# design.net
KiCad netlist of a schematic drawn in Altium Designer
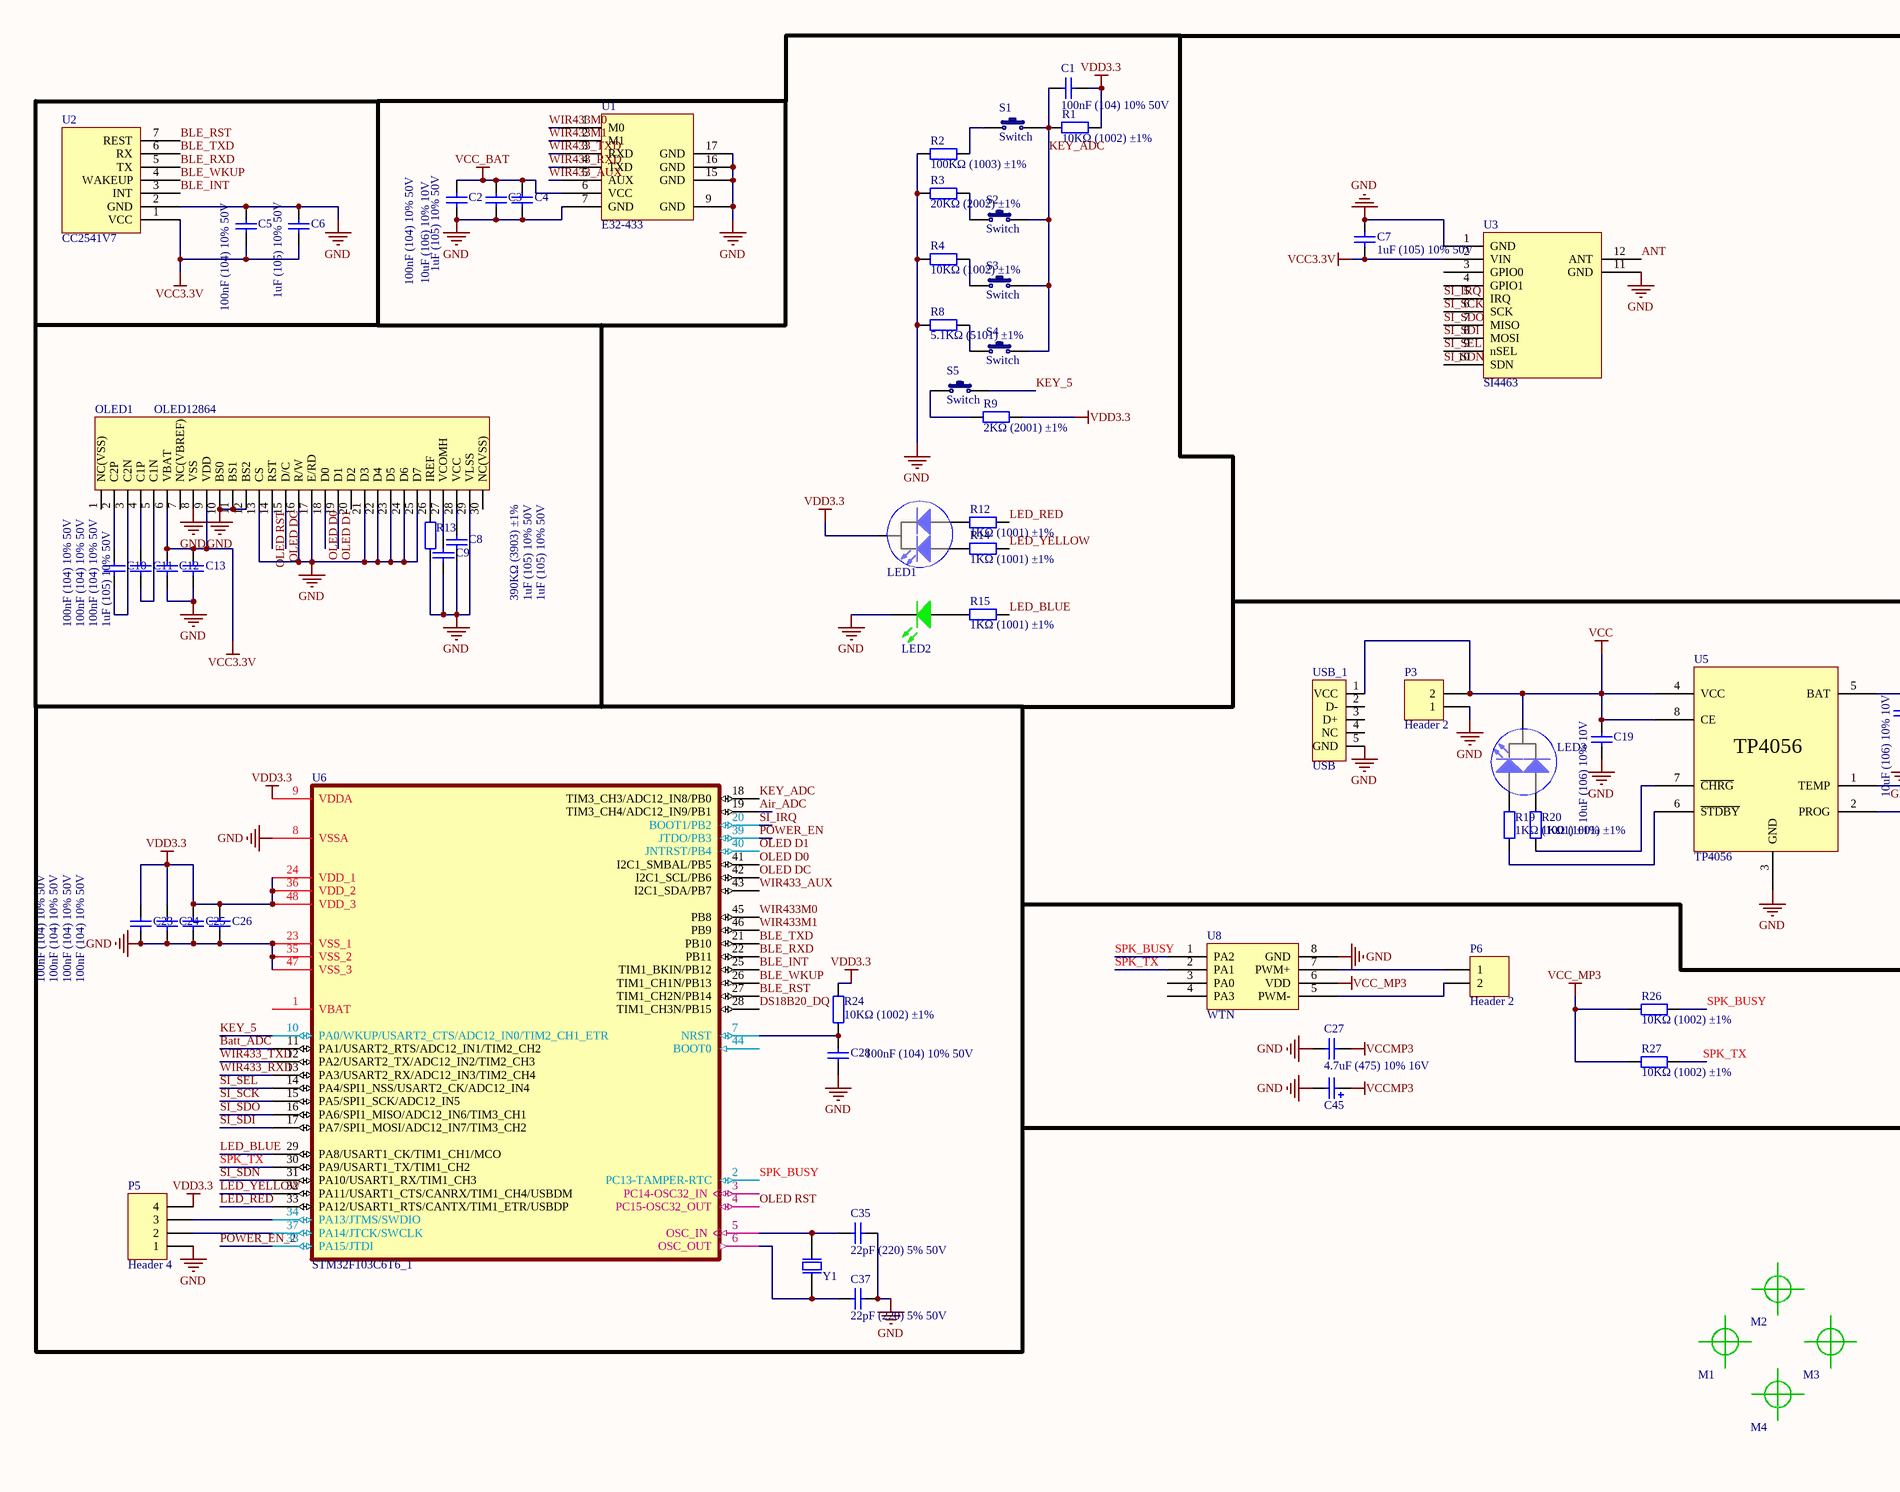
[diagram p0: 消防背表.SchDoc, left]
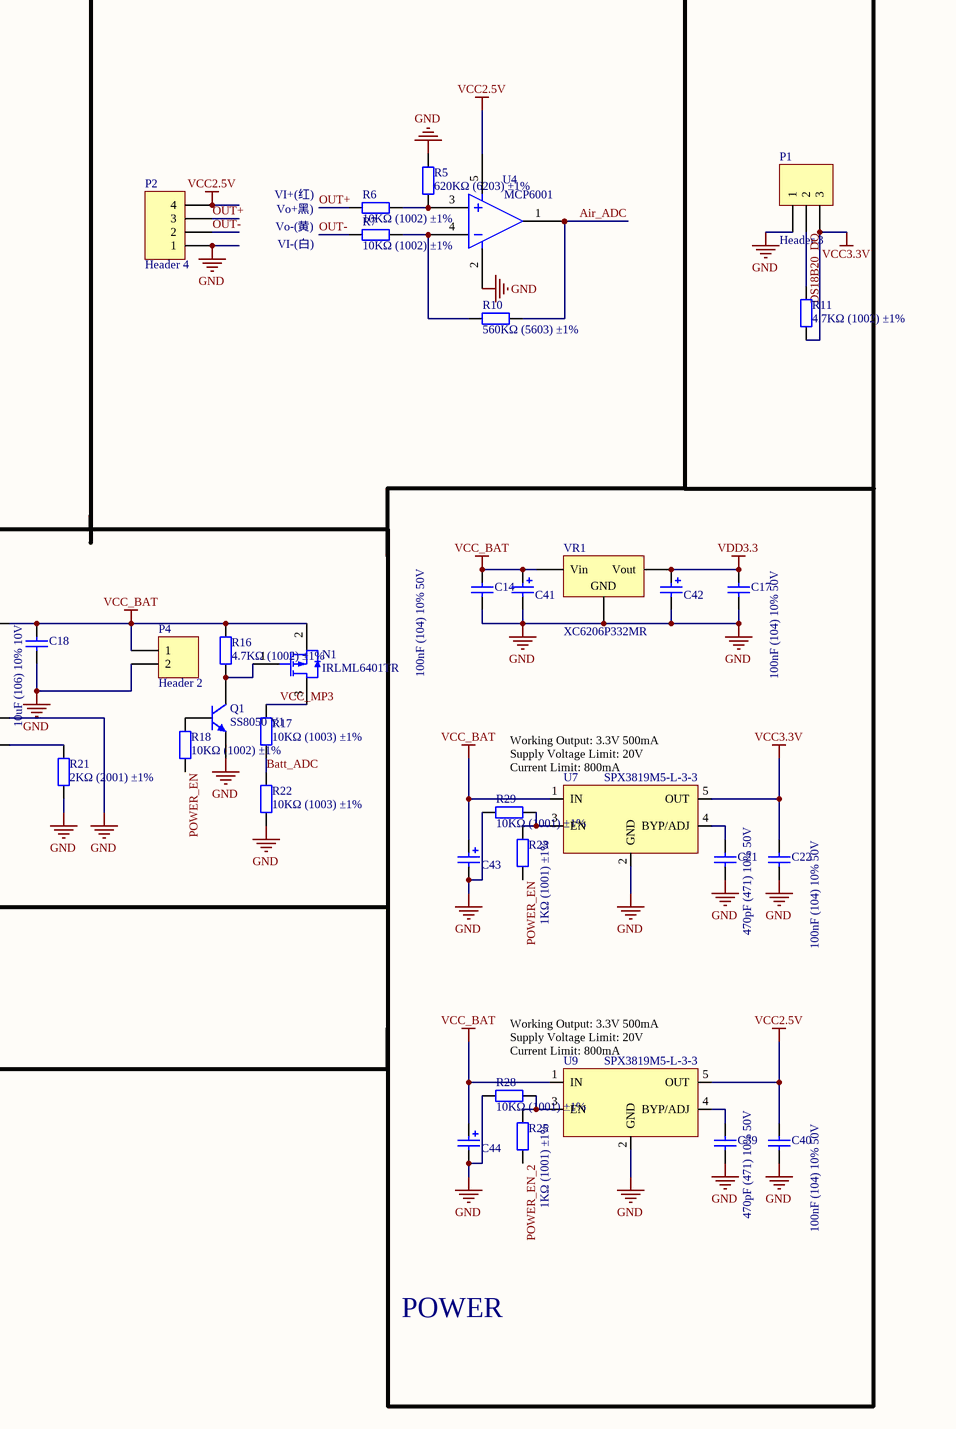
[diagram p1: 消防背表.SchDoc, right]

(export (version "E")
  (design (tool "Eeschema 10.0.6"))
  (components
    (comp (ref "C1")
      (value "100nF (104) 10% 50V")
      (footprint "0603_C")
      (description "贴片电容")
      (libsource (lib "Miscellaneous Devices LC ") (part "0603 100nF (104) 10% 50V"))
    )
    (comp (ref "C2")
      (value "1uF (105) 10% 50V")
      (footprint "0603_C")
      (description "贴片电容")
      (libsource (lib "Miscellaneous Devices LC ") (part "0603 1uF (105) 10% 50V"))
    )
    (comp (ref "C3")
      (value "10uF (106) 10% 10V")
      (footprint "0603_C")
      (description "贴片电容")
      (libsource (lib "Miscellaneous Devices LC ") (part "0603 10uF (106) 10% 10V"))
    )
    (comp (ref "C4")
      (value "100nF (104) 10% 50V")
      (footprint "0603_C")
      (description "贴片电容")
      (libsource (lib "Miscellaneous Devices LC ") (part "0603 100nF (104) 10% 50V"))
    )
    (comp (ref "C5")
      (value "100nF (104) 10% 50V")
      (footprint "0603_C")
      (description "贴片电容")
      (libsource (lib "Miscellaneous Devices LC ") (part "0603 100nF (104) 10% 50V"))
    )
    (comp (ref "C6")
      (value "1uF (105) 10% 50V")
      (footprint "0603_C")
      (description "贴片电容")
      (libsource (lib "Miscellaneous Devices LC ") (part "0603 1uF (105) 10% 50V"))
    )
    (comp (ref "C7")
      (value "1uF (105) 10% 50V")
      (footprint "0603_C")
      (description "贴片电容")
      (libsource (lib "Miscellaneous Devices LC ") (part "0603 1uF (105) 10% 50V"))
    )
    (comp (ref "C8")
      (value "1uF (105) 10% 50V")
      (footprint "0603_C")
      (description "贴片电容")
      (libsource (lib "Miscellaneous Devices LC ") (part "0603 1uF (105) 10% 50V"))
    )
    (comp (ref "C9")
      (value "1uF (105) 10% 50V")
      (footprint "0603_C")
      (description "贴片电容")
      (libsource (lib "Miscellaneous Devices LC ") (part "0603 1uF (105) 10% 50V"))
    )
    (comp (ref "C10")
      (value "100nF (104) 10% 50V")
      (footprint "0603_C")
      (description "贴片电容")
      (libsource (lib "Miscellaneous Devices LC ") (part "0603 100nF (104) 10% 50V"))
    )
    (comp (ref "C11")
      (value "100nF (104) 10% 50V")
      (footprint "0603_C")
      (description "贴片电容")
      (libsource (lib "Miscellaneous Devices LC ") (part "0603 100nF (104) 10% 50V"))
    )
    (comp (ref "C12")
      (value "100nF (104) 10% 50V")
      (footprint "0603_C")
      (description "贴片电容")
      (libsource (lib "Miscellaneous Devices LC ") (part "0603 100nF (104) 10% 50V"))
    )
    (comp (ref "C13")
      (value "1uF (105) 10% 50V")
      (footprint "0603_C")
      (description "贴片电容")
      (libsource (lib "Miscellaneous Devices LC ") (part "0603 1uF (105) 10% 50V"))
    )
    (comp (ref "C14")
      (value "100nF (104) 10% 50V")
      (footprint "0603_C")
      (description "贴片电容")
      (libsource (lib "Miscellaneous Devices LC ") (part "0603 100nF (104) 10% 50V"))
    )
    (comp (ref "C17")
      (value "100nF (104) 10% 50V")
      (footprint "0603_C")
      (description "贴片电容")
      (libsource (lib "Miscellaneous Devices LC ") (part "0603 100nF (104) 10% 50V"))
    )
    (comp (ref "C18")
      (value "10uF (106) 10% 10V")
      (footprint "0603_C")
      (description "贴片电容")
      (libsource (lib "Miscellaneous Devices LC ") (part "0603 10uF (106) 10% 10V"))
    )
    (comp (ref "C19")
      (value "10uF (106) 10% 10V")
      (footprint "0603_C")
      (description "贴片电容")
      (libsource (lib "Miscellaneous Devices LC ") (part "0603 10uF (106) 10% 10V"))
    )
    (comp (ref "C21")
      (value "470pF (471) 10% 50V")
      (footprint "0603_C")
      (description "贴片电容")
      (libsource (lib "Miscellaneous Devices LC ") (part "0603 470pF (471) 10% 50V"))
    )
    (comp (ref "C22")
      (value "100nF (104) 10% 50V")
      (footprint "0603_C")
      (description "贴片电容")
      (libsource (lib "Miscellaneous Devices LC ") (part "0603 100nF (104) 10% 50V"))
    )
    (comp (ref "C23")
      (value "100nF (104) 10% 50V")
      (footprint "0603_C")
      (description "贴片电容")
      (libsource (lib "Miscellaneous Devices LC ") (part "0603 100nF (104) 10% 50V"))
    )
    (comp (ref "C24")
      (value "100nF (104) 10% 50V")
      (footprint "0603_C")
      (description "贴片电容")
      (libsource (lib "Miscellaneous Devices LC ") (part "0603 100nF (104) 10% 50V"))
    )
    (comp (ref "C25")
      (value "100nF (104) 10% 50V")
      (footprint "0603_C")
      (description "贴片电容")
      (libsource (lib "Miscellaneous Devices LC ") (part "0603 100nF (104) 10% 50V"))
    )
    (comp (ref "C26")
      (value "100nF (104) 10% 50V")
      (footprint "0603_C")
      (description "贴片电容")
      (libsource (lib "Miscellaneous Devices LC ") (part "0603 100nF (104) 10% 50V"))
    )
    (comp (ref "C27")
      (value "4.7uF (475) 10% 16V")
      (footprint "0603_C")
      (description "贴片电容")
      (libsource (lib "Miscellaneous Devices LC ") (part "0603 4.7uF (475) 10% 16V"))
    )
    (comp (ref "C28")
      (value "100nF (104) 10% 50V")
      (footprint "0603_C")
      (description "贴片电容")
      (libsource (lib "Miscellaneous Devices LC ") (part "0603 100nF (104) 10% 50V"))
    )
    (comp (ref "C35")
      (value "22pF (220) 5% 50V")
      (footprint "0603_C")
      (description "贴片电容")
      (libsource (lib "Miscellaneous Devices LC ") (part "0603 22pF (220) 5% 50V"))
    )
    (comp (ref "C37")
      (value "22pF (220) 5% 50V")
      (footprint "0603_C")
      (description "贴片电容")
      (libsource (lib "Miscellaneous Devices LC ") (part "0603 22pF (220) 5% 50V"))
    )
    (comp (ref "C39")
      (value "470pF (471) 10% 50V")
      (footprint "0603_C")
      (description "贴片电容")
      (libsource (lib "Miscellaneous Devices LC ") (part "0603 470pF (471) 10% 50V"))
    )
    (comp (ref "C40")
      (value "100nF (104) 10% 50V")
      (footprint "0603_C")
      (description "贴片电容")
      (libsource (lib "Miscellaneous Devices LC ") (part "0603 100nF (104) 10% 50V"))
    )
    (comp (ref "C41")
      (value "Cap Tan")
      (footprint "TAN-A-3216")
      (description "Polarized Capacitor (Radial)")
      (fields (field (name "VOLTAGE") "16V") (field (name "PUBLISHER") "Altium Limited"))
      (libsource (lib "(NEW)DRC_MD Library") (part "Cap Tan"))
    )
    (comp (ref "C42")
      (value "Cap Tan")
      (footprint "TAN-A-3216")
      (description "Polarized Capacitor (Radial)")
      (fields (field (name "VOLTAGE") "16V") (field (name "PUBLISHER") "Altium Limited"))
      (libsource (lib "(NEW)DRC_MD Library") (part "Cap Tan"))
    )
    (comp (ref "C43")
      (value "Cap Tan")
      (footprint "TAN-A-3216")
      (description "Polarized Capacitor (Radial)")
      (fields (field (name "VOLTAGE") "16V") (field (name "PUBLISHER") "Altium Limited"))
      (libsource (lib "(NEW)DRC_MD Library") (part "Cap Tan"))
    )
    (comp (ref "C44")
      (value "Cap Tan")
      (footprint "TAN-A-3216")
      (description "Polarized Capacitor (Radial)")
      (fields (field (name "VOLTAGE") "16V") (field (name "PUBLISHER") "Altium Limited"))
      (libsource (lib "(NEW)DRC_MD Library") (part "Cap Tan"))
    )
    (comp (ref "C45")
      (value "Cap Tan")
      (footprint "TAN-A-3216")
      (description "Polarized Capacitor (Radial)")
      (fields (field (name "VOLTAGE") "16V") (field (name "PUBLISHER") "Altium Limited"))
      (libsource (lib "(NEW)DRC_MD Library") (part "Cap Tan"))
    )
    (comp (ref "LED1")
      (value "LED-3-DOUBLE")
      (footprint "LED-R3-H5-DOUBLE")
      (description "Typical INFRARED GaAs LED")
      (fields (field (name "PUBLISHER") "Altium Limited"))
      (libsource (lib "(NEW)DRC_MD Library") (part "LED-3-DOUBLE"))
    )
    (comp (ref "LED2")
      (value "LED-3-G")
      (footprint "LED-R3-H5-SINGLE-G")
      (description "Typical INFRARED GaAs LED")
      (fields (field (name "PUBLISHER") "Altium Limited"))
      (libsource (lib "(NEW)DRC_MD Library") (part "LED-3-G"))
    )
    (comp (ref "LED3")
      (value "LED-3-DOUBLE")
      (footprint "LED-R3-H5-DOUBLE")
      (description "Typical INFRARED GaAs LED")
      (fields (field (name "PUBLISHER") "Altium Limited"))
      (libsource (lib "(NEW)DRC_MD Library") (part "LED-3-DOUBLE"))
    )
    (comp (ref "M1")
      (value "Screw Hole")
      (footprint "Screw hexagon 3mm")
      (libsource (lib "(NEW)DRC_MD Library") (part "Screw Hole"))
    )
    (comp (ref "M2")
      (value "Screw Hole")
      (footprint "Screw hexagon 3mm")
      (libsource (lib "(NEW)DRC_MD Library") (part "Screw Hole"))
    )
    (comp (ref "M3")
      (value "Screw Hole")
      (footprint "Screw hexagon 3mm")
      (libsource (lib "(NEW)DRC_MD Library") (part "Screw Hole"))
    )
    (comp (ref "M4")
      (value "Screw Hole")
      (footprint "Screw hexagon 3mm")
      (libsource (lib "(NEW)DRC_MD Library") (part "Screw Hole"))
    )
    (comp (ref "N1")
      (value "IRLML6401TR")
      (footprint "SOT23-3")
      (fields (field (name "Comment") "P-MOS"))
      (libsource (lib "kooloo_V1.0") (part "P-MOS"))
    )
    (comp (ref "OLED1")
      (value "OLED12864")
      (footprint "OLED_0.96")
      (libsource (lib "封装库整理") (part "OLED12864"))
    )
    (comp (ref "P1")
      (value "Header 3")
      (footprint "HX2.54-3")
      (description "Header, 3-Pin")
      (fields (field (name "PUBLISHER") "Altium Limited"))
      (libsource (lib "(NEW)DRC_MD Library") (part "Header 3"))
    )
    (comp (ref "P2")
      (value "Header 4")
      (footprint "HX2.54-4")
      (description "Header, 4-Pin")
      (fields (field (name "PUBLISHER") "Altium Limited"))
      (libsource (lib "(NEW)DRC_MD Library") (part "Header 4"))
    )
    (comp (ref "P3")
      (value "Header 2")
      (footprint "HDR1X2")
      (description "Header, 2-Pin")
      (fields (field (name "PUBLISHER") "Altium Limited"))
      (libsource (lib "(NEW)DRC_MD Library") (part "Header 2"))
    )
    (comp (ref "P4")
      (value "Header 2")
      (footprint "HDR1X2")
      (description "Header, 2-Pin")
      (fields (field (name "PUBLISHER") "Altium Limited"))
      (libsource (lib "") (part "Header 2_1"))
    )
    (comp (ref "P5")
      (value "Header 4")
      (footprint "HDR1X4")
      (description "Header, 4-Pin")
      (fields (field (name "PUBLISHER") "Altium Limited"))
      (libsource (lib "(NEW)DRC_MD Library") (part "Header 4"))
    )
    (comp (ref "P6")
      (value "Header 2")
      (footprint "HDR1X2")
      (description "Header, 2-Pin")
      (fields (field (name "PUBLISHER") "Altium Limited"))
      (libsource (lib "") (part "Header 2_1"))
    )
    (comp (ref "Q1")
      (value "SS8050 Y1")
      (footprint "SOT-23(SOT-23-3)")
      (description "三极管")
      (libsource (lib "Miscellaneous Devices LC ") (part "SOT-23 SS8050 Y1"))
    )
    (comp (ref "R1")
      (value "10KΩ (1002) ±1%")
      (footprint "0603_R")
      (description "贴片电阻")
      (libsource (lib "") (part "0603 10KΩ (1002) 1%_1"))
    )
    (comp (ref "R2")
      (value "100KΩ (1003) ±1%")
      (footprint "0603_R")
      (description "贴片电阻")
      (libsource (lib "") (part "0603 100KΩ (1003) 1%_1"))
    )
    (comp (ref "R3")
      (value "20KΩ (2002) ±1%")
      (footprint "0603_R")
      (description "贴片电阻")
      (libsource (lib "Miscellaneous Devices LC ") (part "0603 20KΩ (2002) 1%"))
    )
    (comp (ref "R4")
      (value "10KΩ (1002) ±1%")
      (footprint "0603_R")
      (description "贴片电阻")
      (libsource (lib "") (part "0603 10KΩ (1002) 1%_1"))
    )
    (comp (ref "R5")
      (value "620KΩ (6203) ±1%")
      (footprint "0603_R")
      (description "贴片电阻")
      (libsource (lib "Miscellaneous Devices LC ") (part "0603 620KΩ (6203) 1%"))
    )
    (comp (ref "R6")
      (value "10KΩ (1002) ±1%")
      (footprint "0603_R")
      (description "贴片电阻")
      (libsource (lib "") (part "0603 10KΩ (1002) 1%_1"))
    )
    (comp (ref "R7")
      (value "10KΩ (1002) ±1%")
      (footprint "0603_R")
      (description "贴片电阻")
      (libsource (lib "") (part "0603 10KΩ (1002) 1%_1"))
    )
    (comp (ref "R8")
      (value "5.1KΩ (5101) ±1%")
      (footprint "0603_R")
      (description "贴片电阻")
      (libsource (lib "Miscellaneous Devices LC ") (part "0603 5.1KΩ (5101) 1%"))
    )
    (comp (ref "R9")
      (value "2KΩ (2001) ±1%")
      (footprint "0603_R")
      (description "贴片电阻")
      (libsource (lib "Miscellaneous Devices LC ") (part "0603 2KΩ (2001) 1%"))
    )
    (comp (ref "R10")
      (value "560KΩ (5603) ±1%")
      (footprint "0603_R")
      (description "贴片电阻")
      (libsource (lib "Miscellaneous Devices LC ") (part "0603 560KΩ (5603) 1%"))
    )
    (comp (ref "R11")
      (value "4.7KΩ (1002) ±1%")
      (footprint "0603_R")
      (description "贴片电阻")
      (libsource (lib "Miscellaneous Devices LC ") (part "0603 10KΩ (1002) 1%"))
    )
    (comp (ref "R12")
      (value "1KΩ (1001) ±1%")
      (footprint "0603_R")
      (description "贴片电阻")
      (libsource (lib "Miscellaneous Devices LC ") (part "0603 1KΩ (1001) 1%"))
    )
    (comp (ref "R13")
      (value "390KΩ (3903) ±1%")
      (footprint "0603_R")
      (description "贴片电阻")
      (libsource (lib "Miscellaneous Devices LC ") (part "0603 390KΩ (3903) 1%"))
    )
    (comp (ref "R14")
      (value "1KΩ (1001) ±1%")
      (footprint "0603_R")
      (description "贴片电阻")
      (libsource (lib "Miscellaneous Devices LC ") (part "0603 1KΩ (1001) 1%"))
    )
    (comp (ref "R15")
      (value "1KΩ (1001) ±1%")
      (footprint "0603_R")
      (description "贴片电阻")
      (libsource (lib "Miscellaneous Devices LC ") (part "0603 1KΩ (1001) 1%"))
    )
    (comp (ref "R16")
      (value "4.7KΩ (1002) ±1%")
      (footprint "0603_R")
      (description "贴片电阻")
      (libsource (lib "Miscellaneous Devices LC ") (part "0603 10KΩ (1002) 1%"))
    )
    (comp (ref "R17")
      (value "10KΩ (1003) ±1%")
      (footprint "0603_R")
      (description "贴片电阻")
      (libsource (lib "Miscellaneous Devices LC ") (part "0603 100KΩ (1003) 1%"))
    )
    (comp (ref "R18")
      (value "10KΩ (1002) ±1%")
      (footprint "0603_R")
      (description "贴片电阻")
      (libsource (lib "Miscellaneous Devices LC ") (part "0603 10KΩ (1002) 1%"))
    )
    (comp (ref "R19")
      (value "1KΩ (1001) ±1%")
      (footprint "0603_R")
      (description "贴片电阻")
      (libsource (lib "") (part "0603 1KΩ (1001) 1%_2"))
    )
    (comp (ref "R20")
      (value "1KΩ (1001) ±1%")
      (footprint "0603_R")
      (description "贴片电阻")
      (libsource (lib "") (part "0603 1KΩ (1001) 1%_2"))
    )
    (comp (ref "R21")
      (value "2KΩ (2001) ±1%")
      (footprint "0603_R")
      (description "贴片电阻")
      (libsource (lib "") (part "0603 2KΩ (2001) 1%_1"))
    )
    (comp (ref "R22")
      (value "10KΩ (1003) ±1%")
      (footprint "0603_R")
      (description "贴片电阻")
      (libsource (lib "Miscellaneous Devices LC ") (part "0603 100KΩ (1003) 1%"))
    )
    (comp (ref "R23")
      (value "1KΩ (1001) ±1%")
      (footprint "0603_R")
      (description "贴片电阻")
      (libsource (lib "") (part "0603 1KΩ (1001) 1%_3"))
    )
    (comp (ref "R24")
      (value "10KΩ (1002) ±1%")
      (footprint "0603_R")
      (description "贴片电阻")
      (libsource (lib "") (part "0603 10KΩ (1002) 1%_2"))
    )
    (comp (ref "R25")
      (value "1KΩ (1001) ±1%")
      (footprint "0603_R")
      (description "贴片电阻")
      (libsource (lib "") (part "0603 1KΩ (1001) 1%_3"))
    )
    (comp (ref "R26")
      (value "10KΩ (1002) ±1%")
      (footprint "0603_R")
      (description "贴片电阻")
      (libsource (lib "Miscellaneous Devices LC ") (part "0603 1KΩ (1001) 1%"))
    )
    (comp (ref "R27")
      (value "10KΩ (1002) ±1%")
      (footprint "0603_R")
      (description "贴片电阻")
      (libsource (lib "Miscellaneous Devices LC ") (part "0603 1KΩ (1001) 1%"))
    )
    (comp (ref "R28")
      (value "10KΩ (1001) ±1%")
      (footprint "0603_R")
      (description "贴片电阻")
      (libsource (lib "") (part "0603 1KΩ (1001) 1%_1"))
    )
    (comp (ref "R29")
      (value "10KΩ (1001) ±1%")
      (footprint "0603_R")
      (description "贴片电阻")
      (libsource (lib "") (part "0603 1KΩ (1001) 1%_1"))
    )
    (comp (ref "S1") (value "Switch") (footprint "Switch1") (libsource (lib "Common Device") (part "Switch")))
    (comp (ref "S2") (value "Switch") (footprint "Switch1") (libsource (lib "Common Device") (part "Switch")))
    (comp (ref "S3") (value "Switch") (footprint "Switch1") (libsource (lib "Common Device") (part "Switch")))
    (comp (ref "S4") (value "Switch") (footprint "Switch1") (libsource (lib "Common Device") (part "Switch")))
    (comp (ref "S5") (value "Switch") (footprint "Switch1") (libsource (lib "Common Device") (part "Switch")))
    (comp (ref "U1") (value "E32-433") (footprint "E32_433") (libsource (lib "si4455") (part "E32-433")))
    (comp (ref "U2") (value "CC2541V7") (footprint "BLE_CC2451") (libsource (lib "si4455") (part "CC2541V7")))
    (comp (ref "U3") (value "SI4463") (footprint "SI4463") (libsource (lib "si4455") (part "SI4463")))
    (comp (ref "U4") (value "MCP6001") (footprint "SOT23-5") (libsource (lib "kooloo_V1.0") (part "MCP6001")))
    (comp (ref "U5") (value "TP4056") (footprint "SOP-8_150mil") (libsource (lib "shenj") (part "TP4056")))
    (comp (ref "U6")
      (value "STM32F103C6T6_1")
      (footprint "LQFP-48")
      (description "STM32 ARM-based 32-bit MCU with 32 Kbytes Flash, 48-pin LQFP, Industrial Temperature")
      (fields (field (name "PUBLISHER") "*"))
      (libsource (lib "元件库") (part "STM32F103C6T6_1"))
    )
    (comp (ref "U7")
      (value "SPX3819M5-L-3-3")
      (footprint "SOT-23-6")
      (description "500mA, Low-Noise LDO Voltage Regulator")
      (libsource (lib "Vowstar_IC_General") (part "SPX3819"))
    )
    (comp (ref "U8") (value "WTN") (footprint "SOP-8_150mil") (libsource (lib "si4455") (part "WTN6")))
    (comp (ref "U9")
      (value "SPX3819M5-L-3-3")
      (footprint "SOT-23-6")
      (description "500mA, Low-Noise LDO Voltage Regulator")
      (libsource (lib "Vowstar_IC_General") (part "SPX3819"))
    )
    (comp (ref "USB_1")
      (value "USB")
      (footprint "USB-MINI-B")
      (libsource (lib "(NEW)DRC_MD Library") (part "USB5"))
    )
    (comp (ref "VR1")
      (value "XC6206P332MR")
      (footprint "SOT-23-3L")
      (description "低压差线性稳压(LDO)")
      (libsource (lib "Miscellaneous Devices LC ") (part "SOT-23 XC6206P332MR"))
    )
    (comp (ref "Y1")
      (value "XTAL")
      (footprint "XTAL-49/U_N")
      (description "Crystal Oscillator")
      (fields (field (name "PUBLISHER") "Altium Limited"))
      (libsource (lib "(NEW)DRC_MD Library") (part "XTAL"))
    )
  )
  (nets
    (net (code "1") (name "/ANT") (class "Default")
      (node (ref "U3") (pin "12") (pinfunction "ANT_12") (pintype "passive"))
    )
    (net (code "2") (name "/Air_ADC") (class "Default")
      (node (ref "R10") (pin "2") (pinfunction "2_2") (pintype "passive"))
      (node (ref "U4") (pin "1") (pintype "passive"))
      (node (ref "U6") (pin "19") (pinfunction "TIM3_CH4/ADC12_IN9/PB1_19") (pintype "bidirectional"))
    )
    (net (code "3") (name "/BLE_INT") (class "Default")
      (node (ref "U2") (pin "3") (pinfunction "INT_3") (pintype "passive"))
      (node (ref "U6") (pin "25") (pinfunction "TIM1_BKIN/PB12_25") (pintype "bidirectional"))
    )
    (net (code "4") (name "/BLE_RST") (class "Default")
      (node (ref "U2") (pin "7") (pinfunction "REST_7") (pintype "passive"))
      (node (ref "U6") (pin "27") (pinfunction "TIM1_CH2N/PB14_27") (pintype "bidirectional"))
    )
    (net (code "5") (name "/BLE_RXD") (class "Default")
      (node (ref "U2") (pin "5") (pinfunction "TX_5") (pintype "passive"))
      (node (ref "U6") (pin "22") (pinfunction "PB11_22") (pintype "bidirectional"))
    )
    (net (code "6") (name "/BLE_TXD") (class "Default")
      (node (ref "U2") (pin "6") (pinfunction "RX_6") (pintype "passive"))
      (node (ref "U6") (pin "21") (pinfunction "PB10_21") (pintype "bidirectional"))
    )
    (net (code "7") (name "/BLE_WKUP") (class "Default")
      (node (ref "U2") (pin "4") (pinfunction "WAKEUP_4") (pintype "passive"))
      (node (ref "U6") (pin "26") (pinfunction "TIM1_CH1N/PB13_26") (pintype "bidirectional"))
    )
    (net (code "8") (name "/Batt_ADC") (class "Default")
      (node (ref "R17") (pin "1") (pinfunction "1_1") (pintype "passive"))
      (node (ref "R22") (pin "2") (pinfunction "2_2") (pintype "passive"))
      (node (ref "U6") (pin "11") (pinfunction "PA1/USART2_RTS/ADC12_IN1/TIM2_CH2_11") (pintype "bidirectional"))
    )
    (net (code "9") (name "/DS18B20_DQ") (class "Default")
      (node (ref "P1") (pin "2") (pinfunction "2_2") (pintype "passive"))
      (node (ref "R11") (pin "1") (pinfunction "1_1") (pintype "passive"))
      (node (ref "U6") (pin "28") (pinfunction "TIM1_CH3N/PB15_28") (pintype "bidirectional"))
    )
    (net (code "10") (name "/KEY_5") (class "Default")
      (node (ref "S5") (pin "2") (pinfunction "1_2") (pintype "passive"))
      (node (ref "U6") (pin "10") (pinfunction "PA0/WKUP/USART2_CTS/ADC12_IN0/TIM2_CH1_ETR_10") (pintype "bidirectional"))
    )
    (net (code "11") (name "/KEY_ADC") (class "Default")
      (node (ref "C1") (pin "2") (pinfunction "2_2") (pintype "passive"))
      (node (ref "R1") (pin "1") (pinfunction "1_1") (pintype "passive"))
      (node (ref "S1") (pin "2") (pinfunction "1_2") (pintype "passive"))
      (node (ref "S2") (pin "2") (pinfunction "1_2") (pintype "passive"))
      (node (ref "S3") (pin "2") (pinfunction "1_2") (pintype "passive"))
      (node (ref "S4") (pin "2") (pinfunction "1_2") (pintype "passive"))
      (node (ref "U6") (pin "18") (pinfunction "TIM3_CH3/ADC12_IN8/PB0_18") (pintype "bidirectional"))
    )
    (net (code "12") (name "/LED_BLUE") (class "Default")
      (node (ref "R15") (pin "1") (pinfunction "1_1") (pintype "passive"))
      (node (ref "U6") (pin "29") (pinfunction "PA8/USART1_CK/TIM1_CH1/MCO_29") (pintype "bidirectional"))
    )
    (net (code "13") (name "/LED_RED") (class "Default")
      (node (ref "R12") (pin "1") (pinfunction "1_1") (pintype "passive"))
      (node (ref "U6") (pin "33") (pinfunction "PA12/USART1_RTS/CANTX/TIM1_ETR/USBDP_33") (pintype "bidirectional"))
    )
    (net (code "14") (name "/LED_YELLOW") (class "Default")
      (node (ref "R14") (pin "1") (pinfunction "1_1") (pintype "passive"))
      (node (ref "U6") (pin "32") (pinfunction "PA11/USART1_CTS/CANRX/TIM1_CH4/USBDM_32") (pintype "bidirectional"))
    )
    (net (code "15") (name "/OLED D0") (class "Default")
      (node (ref "OLED1") (pin "18") (pinfunction "D0_18") (pintype "passive"))
      (node (ref "U6") (pin "41") (pinfunction "I2C1_SMBAL/PB5_41") (pintype "bidirectional"))
    )
    (net (code "16") (name "/OLED D1") (class "Default")
      (node (ref "OLED1") (pin "19") (pinfunction "D1_19") (pintype "passive"))
      (node (ref "U6") (pin "40") (pinfunction "JNTRST/PB4_40") (pintype "bidirectional"))
    )
    (net (code "17") (name "/OLED DC") (class "Default")
      (node (ref "OLED1") (pin "15") (pinfunction "D/C_15") (pintype "passive"))
      (node (ref "U6") (pin "42") (pinfunction "I2C1_SCL/PB6_42") (pintype "bidirectional"))
    )
    (net (code "18") (name "/OLED RST") (class "Default")
      (node (ref "OLED1") (pin "14") (pinfunction "RST_14") (pintype "passive"))
      (node (ref "U6") (pin "4") (pinfunction "PC15-OSC32_OUT_4") (pintype "bidirectional"))
    )
    (net (code "19") (name "/OUT+") (class "Default")
      (node (ref "P2") (pin "3") (pinfunction "3_3") (pintype "passive"))
      (node (ref "R6") (pin "1") (pinfunction "1_1") (pintype "passive"))
    )
    (net (code "20") (name "/OUT-") (class "Default")
      (node (ref "P2") (pin "2") (pinfunction "2_2") (pintype "passive"))
      (node (ref "R7") (pin "1") (pinfunction "1_1") (pintype "passive"))
    )
    (net (code "21") (name "/POWER_EN") (class "Default")
      (node (ref "R18") (pin "2") (pinfunction "2_2") (pintype "passive"))
      (node (ref "R23") (pin "2") (pinfunction "2_2") (pintype "passive"))
      (node (ref "U6") (pin "39") (pinfunction "JTDO/PB3_39") (pintype "bidirectional"))
    )
    (net (code "22") (name "/POWER_EN_2") (class "Default")
      (node (ref "R25") (pin "2") (pinfunction "2_2") (pintype "passive"))
      (node (ref "U6") (pin "38") (pinfunction "PA15/JTDI_38") (pintype "bidirectional"))
    )
    (net (code "23") (name "/SI_IRQ") (class "Default")
      (node (ref "U3") (pin "5") (pinfunction "IRQ_5") (pintype "passive"))
      (node (ref "U6") (pin "20") (pinfunction "BOOT1/PB2_20") (pintype "bidirectional"))
    )
    (net (code "24") (name "/SI_SCK") (class "Default")
      (node (ref "U3") (pin "6") (pinfunction "SCK_6") (pintype "passive"))
      (node (ref "U6") (pin "15") (pinfunction "PA5/SPI1_SCK/ADC12_IN5_15") (pintype "bidirectional"))
    )
    (net (code "25") (name "/SI_SDI") (class "Default")
      (node (ref "U3") (pin "8") (pinfunction "MOSI_8") (pintype "passive"))
      (node (ref "U6") (pin "17") (pinfunction "PA7/SPI1_MOSI/ADC12_IN7/TIM3_CH2_17") (pintype "bidirectional"))
    )
    (net (code "26") (name "/SI_SDN") (class "Default")
      (node (ref "U3") (pin "10") (pinfunction "SDN_10") (pintype "passive"))
      (node (ref "U6") (pin "31") (pinfunction "PA10/USART1_RX/TIM1_CH3_31") (pintype "bidirectional"))
    )
    (net (code "27") (name "/SI_SDO") (class "Default")
      (node (ref "U3") (pin "7") (pinfunction "MISO_7") (pintype "passive"))
      (node (ref "U6") (pin "16") (pinfunction "PA6/SPI1_MISO/ADC12_IN6/TIM3_CH1_16") (pintype "bidirectional"))
    )
    (net (code "28") (name "/SI_SEL") (class "Default")
      (node (ref "U3") (pin "9") (pinfunction "nSEL_9") (pintype "passive"))
      (node (ref "U6") (pin "14") (pinfunction "PA4/SPI1_NSS/USART2_CK/ADC12_IN4_14") (pintype "bidirectional"))
    )
    (net (code "29") (name "/SPK_BUSY") (class "Default")
      (node (ref "R26") (pin "1") (pinfunction "1_1") (pintype "passive"))
      (node (ref "U6") (pin "2") (pinfunction "PC13-TAMPER-RTC_2") (pintype "bidirectional"))
      (node (ref "U8") (pin "1") (pinfunction "PA2_1") (pintype "passive"))
    )
    (net (code "30") (name "/SPK_TX") (class "Default")
      (node (ref "R27") (pin "1") (pinfunction "1_1") (pintype "passive"))
      (node (ref "U6") (pin "30") (pinfunction "PA9/USART1_TX/TIM1_CH2_30") (pintype "bidirectional"))
      (node (ref "U8") (pin "2") (pinfunction "PA1_2") (pintype "passive"))
    )
    (net (code "31") (name "/WIR433M0") (class "Default")
      (node (ref "U1") (pin "1") (pinfunction "M0_1") (pintype "passive"))
      (node (ref "U6") (pin "45") (pinfunction "PB8_45") (pintype "bidirectional"))
    )
    (net (code "32") (name "/WIR433M1") (class "Default")
      (node (ref "U1") (pin "2") (pinfunction "M1_2") (pintype "passive"))
      (node (ref "U6") (pin "46") (pinfunction "PB9_46") (pintype "bidirectional"))
    )
    (net (code "33") (name "/WIR433_AUX") (class "Default")
      (node (ref "U1") (pin "5") (pinfunction "AUX_5") (pintype "passive"))
      (node (ref "U6") (pin "43") (pinfunction "I2C1_SDA/PB7_43") (pintype "bidirectional"))
    )
    (net (code "34") (name "/WIR433_RXD") (class "Default")
      (node (ref "U1") (pin "4") (pinfunction "TXD_4") (pintype "passive"))
      (node (ref "U6") (pin "13") (pinfunction "PA3/USART2_RX/ADC12_IN3/TIM2_CH4_13") (pintype "bidirectional"))
    )
    (net (code "35") (name "/WIR433_TXD") (class "Default")
      (node (ref "U1") (pin "3") (pinfunction "RXD_3") (pintype "passive"))
      (node (ref "U6") (pin "12") (pinfunction "PA2/USART2_TX/ADC12_IN2/TIM2_CH3_12") (pintype "bidirectional"))
    )
    (net (code "36") (name "GND") (class "Default")
      (node (ref "C12") (pin "1") (pinfunction "1_1") (pintype "passive"))
      (node (ref "C13") (pin "1") (pinfunction "1_1") (pintype "passive"))
      (node (ref "C14") (pin "1") (pinfunction "1_1") (pintype "passive"))
      (node (ref "C17") (pin "1") (pinfunction "1_1") (pintype "passive"))
      (node (ref "C18") (pin "1") (pinfunction "1_1") (pintype "passive"))
      (node (ref "C19") (pin "1") (pinfunction "1_1") (pintype "passive"))
      (node (ref "C2") (pin "1") (pinfunction "1_1") (pintype "passive"))
      (node (ref "C21") (pin "1") (pinfunction "1_1") (pintype "passive"))
      (node (ref "C22") (pin "1") (pinfunction "1_1") (pintype "passive"))
      (node (ref "C23") (pin "1") (pinfunction "1_1") (pintype "passive"))
      (node (ref "C24") (pin "1") (pinfunction "1_1") (pintype "passive"))
      (node (ref "C25") (pin "1") (pinfunction "1_1") (pintype "passive"))
      (node (ref "C26") (pin "1") (pinfunction "1_1") (pintype "passive"))
      (node (ref "C27") (pin "2") (pinfunction "2_2") (pintype "passive"))
      (node (ref "C28") (pin "1") (pinfunction "1_1") (pintype "passive"))
      (node (ref "C3") (pin "1") (pinfunction "1_1") (pintype "passive"))
      (node (ref "C35") (pin "2") (pinfunction "2_2") (pintype "passive"))
      (node (ref "C37") (pin "2") (pinfunction "2_2") (pintype "passive"))
      (node (ref "C39") (pin "1") (pinfunction "1_1") (pintype "passive"))
      (node (ref "C4") (pin "1") (pinfunction "1_1") (pintype "passive"))
      (node (ref "C40") (pin "1") (pinfunction "1_1") (pintype "passive"))
      (node (ref "C41") (pin "1") (pinfunction "2_1") (pintype "passive"))
      (node (ref "C42") (pin "1") (pinfunction "2_1") (pintype "passive"))
      (node (ref "C43") (pin "1") (pinfunction "2_1") (pintype "passive"))
      (node (ref "C44") (pin "1") (pinfunction "2_1") (pintype "passive"))
      (node (ref "C45") (pin "1") (pinfunction "2_1") (pintype "passive"))
      (node (ref "C5") (pin "2") (pinfunction "2_2") (pintype "passive"))
      (node (ref "C6") (pin "2") (pinfunction "2_2") (pintype "passive"))
      (node (ref "C7") (pin "1") (pinfunction "1_1") (pintype "passive"))
      (node (ref "C8") (pin "1") (pinfunction "1_1") (pintype "passive"))
      (node (ref "C9") (pin "1") (pinfunction "1_1") (pintype "passive"))
      (node (ref "LED2") (pin "2") (pinfunction "K_2") (pintype "passive"))
      (node (ref "OLED1") (pin "10") (pinfunction "BS0_10") (pintype "passive"))
      (node (ref "OLED1") (pin "11") (pinfunction "BS1_11") (pintype "passive"))
      (node (ref "OLED1") (pin "12") (pinfunction "BS2_12") (pintype "passive"))
      (node (ref "OLED1") (pin "13") (pinfunction "CS_13") (pintype "passive"))
      (node (ref "OLED1") (pin "16") (pinfunction "R/W_16") (pintype "passive"))
      (node (ref "OLED1") (pin "17") (pinfunction "E/RD_17") (pintype "passive"))
      (node (ref "OLED1") (pin "21") (pinfunction "D3_21") (pintype "passive"))
      (node (ref "OLED1") (pin "22") (pinfunction "D4_22") (pintype "passive"))
      (node (ref "OLED1") (pin "23") (pinfunction "D5_23") (pintype "passive"))
      (node (ref "OLED1") (pin "24") (pinfunction "D6_24") (pintype "passive"))
      (node (ref "OLED1") (pin "25") (pinfunction "D7_25") (pintype "passive"))
      (node (ref "OLED1") (pin "29") (pinfunction "VLSS_29") (pintype "passive"))
      (node (ref "OLED1") (pin "8") (pinfunction "VSS_8") (pintype "passive"))
      (node (ref "P1") (pin "1") (pinfunction "1_1") (pintype "passive"))
      (node (ref "P2") (pin "1") (pinfunction "1_1") (pintype "passive"))
      (node (ref "P3") (pin "1") (pinfunction "1_1") (pintype "passive"))
      (node (ref "P4") (pin "2") (pinfunction "2_2") (pintype "passive"))
      (node (ref "P5") (pin "1") (pinfunction "1_1") (pintype "passive"))
      (node (ref "Q1") (pin "2") (pinfunction "E_2") (pintype "passive"))
      (node (ref "R13") (pin "1") (pinfunction "1_1") (pintype "passive"))
      (node (ref "R2") (pin "1") (pinfunction "1_1") (pintype "passive"))
      (node (ref "R21") (pin "1") (pinfunction "1_1") (pintype "passive"))
      (node (ref "R22") (pin "1") (pinfunction "1_1") (pintype "passive"))
      (node (ref "R28") (pin "1") (pinfunction "1_1") (pintype "passive"))
      (node (ref "R29") (pin "1") (pinfunction "1_1") (pintype "passive"))
      (node (ref "R3") (pin "1") (pinfunction "1_1") (pintype "passive"))
      (node (ref "R4") (pin "1") (pinfunction "1_1") (pintype "passive"))
      (node (ref "R5") (pin "2") (pinfunction "2_2") (pintype "passive"))
      (node (ref "R8") (pin "1") (pinfunction "1_1") (pintype "passive"))
      (node (ref "U1") (pin "15") (pinfunction "GND_15") (pintype "passive"))
      (node (ref "U1") (pin "16") (pinfunction "GND_16") (pintype "passive"))
      (node (ref "U1") (pin "17") (pinfunction "GND_17") (pintype "passive"))
      (node (ref "U1") (pin "7") (pinfunction "GND_7") (pintype "passive"))
      (node (ref "U1") (pin "9") (pinfunction "GND_9") (pintype "passive"))
      (node (ref "U2") (pin "2") (pinfunction "GND_2") (pintype "passive"))
      (node (ref "U3") (pin "1") (pinfunction "GND_1") (pintype "passive"))
      (node (ref "U3") (pin "11") (pinfunction "GND_11") (pintype "passive"))
      (node (ref "U4") (pin "2") (pintype "passive"))
      (node (ref "U5") (pin "1") (pinfunction "TEMP_1") (pintype "passive"))
      (node (ref "U5") (pin "3") (pinfunction "GND_3") (pintype "passive"))
      (node (ref "U6") (pin "23") (pinfunction "VSS_1_23") (pintype "power_in"))
      (node (ref "U6") (pin "35") (pinfunction "VSS_2_35") (pintype "power_in"))
      (node (ref "U6") (pin "47") (pinfunction "VSS_3_47") (pintype "power_in"))
      (node (ref "U6") (pin "8") (pinfunction "VSSA_8") (pintype "power_in"))
      (node (ref "U7") (pin "2") (pinfunction "GND_2") (pintype "passive"))
      (node (ref "U8") (pin "8") (pinfunction "GND_8") (pintype "passive"))
      (node (ref "U9") (pin "2") (pinfunction "GND_2") (pintype "passive"))
      (node (ref "USB_1") (pin "5") (pinfunction "GND_5") (pintype "passive"))
      (node (ref "VR1") (pin "1") (pinfunction "GND_1") (pintype "passive"))
    )
    (net (code "37") (name "Net-(LED1-A-Pad2)") (class "Default")
      (node (ref "LED1") (pin "2") (pinfunction "A_2") (pintype "passive"))
      (node (ref "R14") (pin "2") (pinfunction "2_2") (pintype "passive"))
    )
    (net (code "38") (name "Net-(LED1-A-Pad3)") (class "Default")
      (node (ref "LED1") (pin "3") (pinfunction "A_3") (pintype "passive"))
      (node (ref "R12") (pin "2") (pinfunction "2_2") (pintype "passive"))
    )
    (net (code "39") (name "Net-(LED2-A)") (class "Default")
      (node (ref "LED2") (pin "1") (pinfunction "A_1") (pintype "passive"))
      (node (ref "R15") (pin "2") (pinfunction "2_2") (pintype "passive"))
    )
    (net (code "40") (name "Net-(LED3-A-Pad2)") (class "Default")
      (node (ref "LED3") (pin "2") (pinfunction "A_2") (pintype "passive"))
      (node (ref "R19") (pin "2") (pinfunction "2_2") (pintype "passive"))
    )
    (net (code "41") (name "Net-(LED3-A-Pad3)") (class "Default")
      (node (ref "LED3") (pin "3") (pinfunction "A_3") (pintype "passive"))
      (node (ref "R20") (pin "2") (pinfunction "2_2") (pintype "passive"))
    )
    (net (code "42") (name "Net-(N1-G)") (class "Default")
      (node (ref "N1") (pin "1") (pinfunction "G_1") (pintype "passive"))
      (node (ref "Q1") (pin "3") (pinfunction "C_3") (pintype "passive"))
      (node (ref "R16") (pin "2") (pinfunction "2_2") (pintype "passive"))
    )
    (net (code "43") (name "Net-(OLED1-C1N)") (class "Default")
      (node (ref "C11") (pin "1") (pinfunction "1_1") (pintype "passive"))
      (node (ref "OLED1") (pin "5") (pinfunction "C1N_5") (pintype "passive"))
    )
    (net (code "44") (name "Net-(OLED1-C1P)") (class "Default")
      (node (ref "C11") (pin "2") (pinfunction "2_2") (pintype "passive"))
      (node (ref "OLED1") (pin "4") (pinfunction "C1P_4") (pintype "passive"))
    )
    (net (code "45") (name "Net-(OLED1-C2N)") (class "Default")
      (node (ref "C10") (pin "1") (pinfunction "1_1") (pintype "passive"))
      (node (ref "OLED1") (pin "3") (pinfunction "C2N_3") (pintype "passive"))
    )
    (net (code "46") (name "Net-(OLED1-C2P)") (class "Default")
      (node (ref "C10") (pin "2") (pinfunction "2_2") (pintype "passive"))
      (node (ref "OLED1") (pin "2") (pinfunction "C2P_2") (pintype "passive"))
    )
    (net (code "47") (name "Net-(OLED1-IREF)") (class "Default")
      (node (ref "OLED1") (pin "26") (pinfunction "IREF_26") (pintype "passive"))
      (node (ref "R13") (pin "2") (pinfunction "2_2") (pintype "passive"))
    )
    (net (code "48") (name "Net-(OLED1-VCC)") (class "Default")
      (node (ref "C8") (pin "2") (pinfunction "2_2") (pintype "passive"))
      (node (ref "OLED1") (pin "28") (pinfunction "VCC_28") (pintype "passive"))
    )
    (net (code "49") (name "Net-(OLED1-VCOMH)") (class "Default")
      (node (ref "C9") (pin "2") (pinfunction "2_2") (pintype "passive"))
      (node (ref "OLED1") (pin "27") (pinfunction "VCOMH_27") (pintype "passive"))
    )
    (net (code "50") (name "Net-(Q1-B)") (class "Default")
      (node (ref "Q1") (pin "1") (pinfunction "B_1") (pintype "passive"))
      (node (ref "R18") (pin "1") (pinfunction "1_1") (pintype "passive"))
    )
    (net (code "51") (name "Net-(R5-Pad1)") (class "Default")
      (node (ref "R5") (pin "1") (pinfunction "1_1") (pintype "passive"))
      (node (ref "R6") (pin "2") (pinfunction "2_2") (pintype "passive"))
      (node (ref "U4") (pin "3") (pintype "passive"))
    )
    (net (code "52") (name "Net-(R10-Pad1)") (class "Default")
      (node (ref "R10") (pin "1") (pinfunction "1_1") (pintype "passive"))
      (node (ref "R7") (pin "2") (pinfunction "2_2") (pintype "passive"))
      (node (ref "U4") (pin "4") (pintype "passive"))
    )
    (net (code "53") (name "Net-(S1-0)") (class "Default")
      (node (ref "R2") (pin "2") (pinfunction "2_2") (pintype "passive"))
      (node (ref "S1") (pin "1") (pinfunction "0_1") (pintype "passive"))
    )
    (net (code "54") (name "Net-(S2-0)") (class "Default")
      (node (ref "R3") (pin "2") (pinfunction "2_2") (pintype "passive"))
      (node (ref "S2") (pin "1") (pinfunction "0_1") (pintype "passive"))
    )
    (net (code "55") (name "Net-(S3-0)") (class "Default")
      (node (ref "R4") (pin "2") (pinfunction "2_2") (pintype "passive"))
      (node (ref "S3") (pin "1") (pinfunction "0_1") (pintype "passive"))
    )
    (net (code "56") (name "Net-(S4-0)") (class "Default")
      (node (ref "R8") (pin "2") (pinfunction "2_2") (pintype "passive"))
      (node (ref "S4") (pin "1") (pinfunction "0_1") (pintype "passive"))
    )
    (net (code "57") (name "Net-(S5-0)") (class "Default")
      (node (ref "R9") (pin "1") (pinfunction "1_1") (pintype "passive"))
      (node (ref "S5") (pin "1") (pinfunction "0_1") (pintype "passive"))
    )
    (net (code "58") (name "Net-(U5-PROG)") (class "Default")
      (node (ref "R21") (pin "2") (pinfunction "2_2") (pintype "passive"))
      (node (ref "U5") (pin "2") (pinfunction "PROG_2") (pintype "passive"))
    )
    (net (code "59") (name "Net-(U5-~{CHRG})") (class "Default")
      (node (ref "R20") (pin "1") (pinfunction "1_1") (pintype "passive"))
      (node (ref "U5") (pin "7") (pinfunction "~{CHRG}_7") (pintype "passive"))
    )
    (net (code "60") (name "Net-(U5-~{STDBY})") (class "Default")
      (node (ref "R19") (pin "1") (pinfunction "1_1") (pintype "passive"))
      (node (ref "U5") (pin "6") (pinfunction "~{STDBY}_6") (pintype "passive"))
    )
    (net (code "61") (name "Net-(U6-NRST)") (class "Default")
      (node (ref "C28") (pin "2") (pinfunction "2_2") (pintype "passive"))
      (node (ref "R24") (pin "1") (pinfunction "1_1") (pintype "passive"))
      (node (ref "U6") (pin "7") (pinfunction "NRST_7") (pintype "bidirectional"))
    )
    (net (code "62") (name "Net-(U6-OSC_IN)") (class "Default")
      (node (ref "C35") (pin "1") (pinfunction "1_1") (pintype "passive"))
      (node (ref "U6") (pin "5") (pinfunction "OSC_IN_5") (pintype "input"))
      (node (ref "Y1") (pin "2") (pinfunction "OSC2_2") (pintype "passive"))
    )
    (net (code "63") (name "Net-(U6-OSC_OUT)") (class "Default")
      (node (ref "C37") (pin "1") (pinfunction "1_1") (pintype "passive"))
      (node (ref "U6") (pin "6") (pinfunction "OSC_OUT_6") (pintype "output"))
      (node (ref "Y1") (pin "1") (pinfunction "OSC1_1") (pintype "passive"))
    )
    (net (code "64") (name "Net-(U6-PA13{slash}JTMS{slash}SWDIO)") (class "Default")
      (node (ref "P5") (pin "3") (pinfunction "3_3") (pintype "passive"))
      (node (ref "U6") (pin "34") (pinfunction "PA13/JTMS/SWDIO_34") (pintype "bidirectional"))
    )
    (net (code "65") (name "Net-(U6-PA14{slash}JTCK{slash}SWCLK)") (class "Default")
      (node (ref "P5") (pin "2") (pinfunction "2_2") (pintype "passive"))
      (node (ref "U6") (pin "37") (pinfunction "PA14/JTCK/SWCLK_37") (pintype "bidirectional"))
    )
    (net (code "66") (name "Net-(U7-BYP{slash}ADJ)") (class "Default")
      (node (ref "C21") (pin "2") (pinfunction "2_2") (pintype "passive"))
      (node (ref "U7") (pin "4") (pinfunction "BYP/ADJ_4") (pintype "passive"))
    )
    (net (code "67") (name "Net-(U7-EN)") (class "Default")
      (node (ref "R23") (pin "1") (pinfunction "1_1") (pintype "passive"))
      (node (ref "R29") (pin "2") (pinfunction "2_2") (pintype "passive"))
      (node (ref "U7") (pin "3") (pinfunction "EN_3") (pintype "passive"))
    )
    (net (code "68") (name "Net-(U8-PWM+)") (class "Default")
      (node (ref "P6") (pin "1") (pinfunction "1_1") (pintype "passive"))
      (node (ref "U8") (pin "7") (pinfunction "PWM+_7") (pintype "passive"))
    )
    (net (code "69") (name "Net-(U8-PWM-)") (class "Default")
      (node (ref "P6") (pin "2") (pinfunction "2_2") (pintype "passive"))
      (node (ref "U8") (pin "5") (pinfunction "PWM-_5") (pintype "passive"))
    )
    (net (code "70") (name "Net-(U9-BYP{slash}ADJ)") (class "Default")
      (node (ref "C39") (pin "2") (pinfunction "2_2") (pintype "passive"))
      (node (ref "U9") (pin "4") (pinfunction "BYP/ADJ_4") (pintype "passive"))
    )
    (net (code "71") (name "Net-(U9-EN)") (class "Default")
      (node (ref "R25") (pin "1") (pinfunction "1_1") (pintype "passive"))
      (node (ref "R28") (pin "2") (pinfunction "2_2") (pintype "passive"))
      (node (ref "U9") (pin "3") (pinfunction "EN_3") (pintype "passive"))
    )
    (net (code "72") (name "VCC") (class "Default")
      (node (ref "C19") (pin "2") (pinfunction "2_2") (pintype "passive"))
      (node (ref "LED3") (pin "1") (pinfunction "K_1") (pintype "passive"))
      (node (ref "P3") (pin "2") (pinfunction "2_2") (pintype "passive"))
      (node (ref "U5") (pin "4") (pinfunction "VCC_4") (pintype "passive"))
      (node (ref "U5") (pin "8") (pinfunction "CE_8") (pintype "passive"))
      (node (ref "USB_1") (pin "1") (pinfunction "VCC_1") (pintype "passive"))
    )
    (net (code "73") (name "VCC2.5V") (class "Default")
      (node (ref "C40") (pin "2") (pinfunction "2_2") (pintype "passive"))
      (node (ref "P2") (pin "4") (pinfunction "4_4") (pintype "passive"))
      (node (ref "U4") (pin "5") (pintype "passive"))
      (node (ref "U9") (pin "5") (pinfunction "OUT_5") (pintype "passive"))
    )
    (net (code "74") (name "VCC3.3V") (class "Default")
      (node (ref "C12") (pin "2") (pinfunction "2_2") (pintype "passive"))
      (node (ref "C13") (pin "2") (pinfunction "2_2") (pintype "passive"))
      (node (ref "C22") (pin "2") (pinfunction "2_2") (pintype "passive"))
      (node (ref "C5") (pin "1") (pinfunction "1_1") (pintype "passive"))
      (node (ref "C6") (pin "1") (pinfunction "1_1") (pintype "passive"))
      (node (ref "C7") (pin "2") (pinfunction "2_2") (pintype "passive"))
      (node (ref "OLED1") (pin "6") (pinfunction "VBAT_6") (pintype "passive"))
      (node (ref "OLED1") (pin "9") (pinfunction "VDD_9") (pintype "passive"))
      (node (ref "P1") (pin "3") (pinfunction "3_3") (pintype "passive"))
      (node (ref "R11") (pin "2") (pinfunction "2_2") (pintype "passive"))
      (node (ref "U2") (pin "1") (pinfunction "VCC_1") (pintype "passive"))
      (node (ref "U3") (pin "2") (pinfunction "VIN_2") (pintype "passive"))
      (node (ref "U7") (pin "5") (pinfunction "OUT_5") (pintype "passive"))
    )
    (net (code "75") (name "VCCMP3") (class "Default")
      (node (ref "C27") (pin "1") (pinfunction "1_1") (pintype "passive"))
      (node (ref "C45") (pin "2") (pinfunction "1_2") (pintype "passive"))
    )
    (net (code "76") (name "VCC_BAT") (class "Default")
      (node (ref "C14") (pin "2") (pinfunction "2_2") (pintype "passive"))
      (node (ref "C18") (pin "2") (pinfunction "2_2") (pintype "passive"))
      (node (ref "C2") (pin "2") (pinfunction "2_2") (pintype "passive"))
      (node (ref "C3") (pin "2") (pinfunction "2_2") (pintype "passive"))
      (node (ref "C4") (pin "2") (pinfunction "2_2") (pintype "passive"))
      (node (ref "C41") (pin "2") (pinfunction "1_2") (pintype "passive"))
      (node (ref "C43") (pin "2") (pinfunction "1_2") (pintype "passive"))
      (node (ref "C44") (pin "2") (pinfunction "1_2") (pintype "passive"))
      (node (ref "N1") (pin "2") (pinfunction "S_2") (pintype "passive"))
      (node (ref "P4") (pin "1") (pinfunction "1_1") (pintype "passive"))
      (node (ref "R16") (pin "1") (pinfunction "1_1") (pintype "passive"))
      (node (ref "U1") (pin "6") (pinfunction "VCC_6") (pintype "passive"))
      (node (ref "U5") (pin "5") (pinfunction "BAT_5") (pintype "passive"))
      (node (ref "U7") (pin "1") (pinfunction "IN_1") (pintype "passive"))
      (node (ref "U9") (pin "1") (pinfunction "IN_1") (pintype "passive"))
      (node (ref "VR1") (pin "3") (pinfunction "Vin_3") (pintype "passive"))
    )
    (net (code "77") (name "VCC_MP3") (class "Default")
      (node (ref "N1") (pin "3") (pinfunction "D_3") (pintype "passive"))
      (node (ref "R17") (pin "2") (pinfunction "2_2") (pintype "passive"))
      (node (ref "R26") (pin "2") (pinfunction "2_2") (pintype "passive"))
      (node (ref "R27") (pin "2") (pinfunction "2_2") (pintype "passive"))
      (node (ref "U8") (pin "6") (pinfunction "VDD_6") (pintype "passive"))
    )
    (net (code "78") (name "VDD3.3") (class "Default")
      (node (ref "C1") (pin "1") (pinfunction "1_1") (pintype "passive"))
      (node (ref "C17") (pin "2") (pinfunction "2_2") (pintype "passive"))
      (node (ref "C23") (pin "2") (pinfunction "2_2") (pintype "passive"))
      (node (ref "C24") (pin "2") (pinfunction "2_2") (pintype "passive"))
      (node (ref "C25") (pin "2") (pinfunction "2_2") (pintype "passive"))
      (node (ref "C26") (pin "2") (pinfunction "2_2") (pintype "passive"))
      (node (ref "C42") (pin "2") (pinfunction "1_2") (pintype "passive"))
      (node (ref "LED1") (pin "1") (pinfunction "K_1") (pintype "passive"))
      (node (ref "P5") (pin "4") (pinfunction "4_4") (pintype "passive"))
      (node (ref "R1") (pin "2") (pinfunction "2_2") (pintype "passive"))
      (node (ref "R24") (pin "2") (pinfunction "2_2") (pintype "passive"))
      (node (ref "R9") (pin "2") (pinfunction "2_2") (pintype "passive"))
      (node (ref "U6") (pin "24") (pinfunction "VDD_1_24") (pintype "power_in"))
      (node (ref "U6") (pin "36") (pinfunction "VDD_2_36") (pintype "power_in"))
      (node (ref "U6") (pin "48") (pinfunction "VDD_3_48") (pintype "power_in"))
      (node (ref "U6") (pin "9") (pinfunction "VDDA_9") (pintype "power_in"))
      (node (ref "VR1") (pin "2") (pinfunction "Vout_2") (pintype "passive"))
    )
    (net (code "79") (name "unconnected-(OLED1-D2-Pad20)") (class "Default")
      (node (ref "OLED1") (pin "20") (pinfunction "D2_20") (pintype "passive"))
    )
    (net (code "80") (name "unconnected-(OLED1-NC(VBREF)-Pad7)") (class "Default")
      (node (ref "OLED1") (pin "7") (pinfunction "NC(VBREF)_7") (pintype "passive"))
    )
    (net (code "81") (name "unconnected-(OLED1-NC(VSS)-Pad1)") (class "Default")
      (node (ref "OLED1") (pin "1") (pinfunction "NC(VSS)_1") (pintype "passive"))
    )
    (net (code "82") (name "unconnected-(OLED1-NC(VSS)-Pad30)") (class "Default")
      (node (ref "OLED1") (pin "30") (pinfunction "NC(VSS)_30") (pintype "passive"))
    )
    (net (code "83") (name "unconnected-(U3-GPIO0-Pad3)") (class "Default")
      (node (ref "U3") (pin "3") (pinfunction "GPIO0_3") (pintype "passive"))
    )
    (net (code "84") (name "unconnected-(U3-GPIO1-Pad4)") (class "Default")
      (node (ref "U3") (pin "4") (pinfunction "GPIO1_4") (pintype "passive"))
    )
    (net (code "85") (name "unconnected-(U6-BOOT0-Pad44)") (class "Default")
      (node (ref "U6") (pin "44") (pinfunction "BOOT0_44") (pintype "input"))
    )
    (net (code "86") (name "unconnected-(U6-PC14-OSC32_IN-Pad3)") (class "Default")
      (node (ref "U6") (pin "3") (pinfunction "PC14-OSC32_IN_3") (pintype "bidirectional"))
    )
    (net (code "87") (name "unconnected-(U6-VBAT-Pad1)") (class "Default")
      (node (ref "U6") (pin "1") (pinfunction "VBAT_1") (pintype "power_in"))
    )
    (net (code "88") (name "unconnected-(U8-PA0-Pad3)") (class "Default")
      (node (ref "U8") (pin "3") (pinfunction "PA0_3") (pintype "passive"))
    )
    (net (code "89") (name "unconnected-(U8-PA3-Pad4)") (class "Default")
      (node (ref "U8") (pin "4") (pinfunction "PA3_4") (pintype "passive"))
    )
    (net (code "90") (name "unconnected-(USB_1-D+-Pad3)") (class "Default")
      (node (ref "USB_1") (pin "3") (pinfunction "D+_3") (pintype "passive"))
    )
    (net (code "91") (name "unconnected-(USB_1-D--Pad2)") (class "Default")
      (node (ref "USB_1") (pin "2") (pinfunction "D-_2") (pintype "passive"))
    )
    (net (code "92") (name "unconnected-(USB_1-NC-Pad4)") (class "Default")
      (node (ref "USB_1") (pin "4") (pinfunction "NC_4") (pintype "passive"))
    )
  )
)
